# EVK-NORA-W4_SCHEM_0004_Debug_Memory.net
KiCad netlist of a schematic drawn in Altium Designer
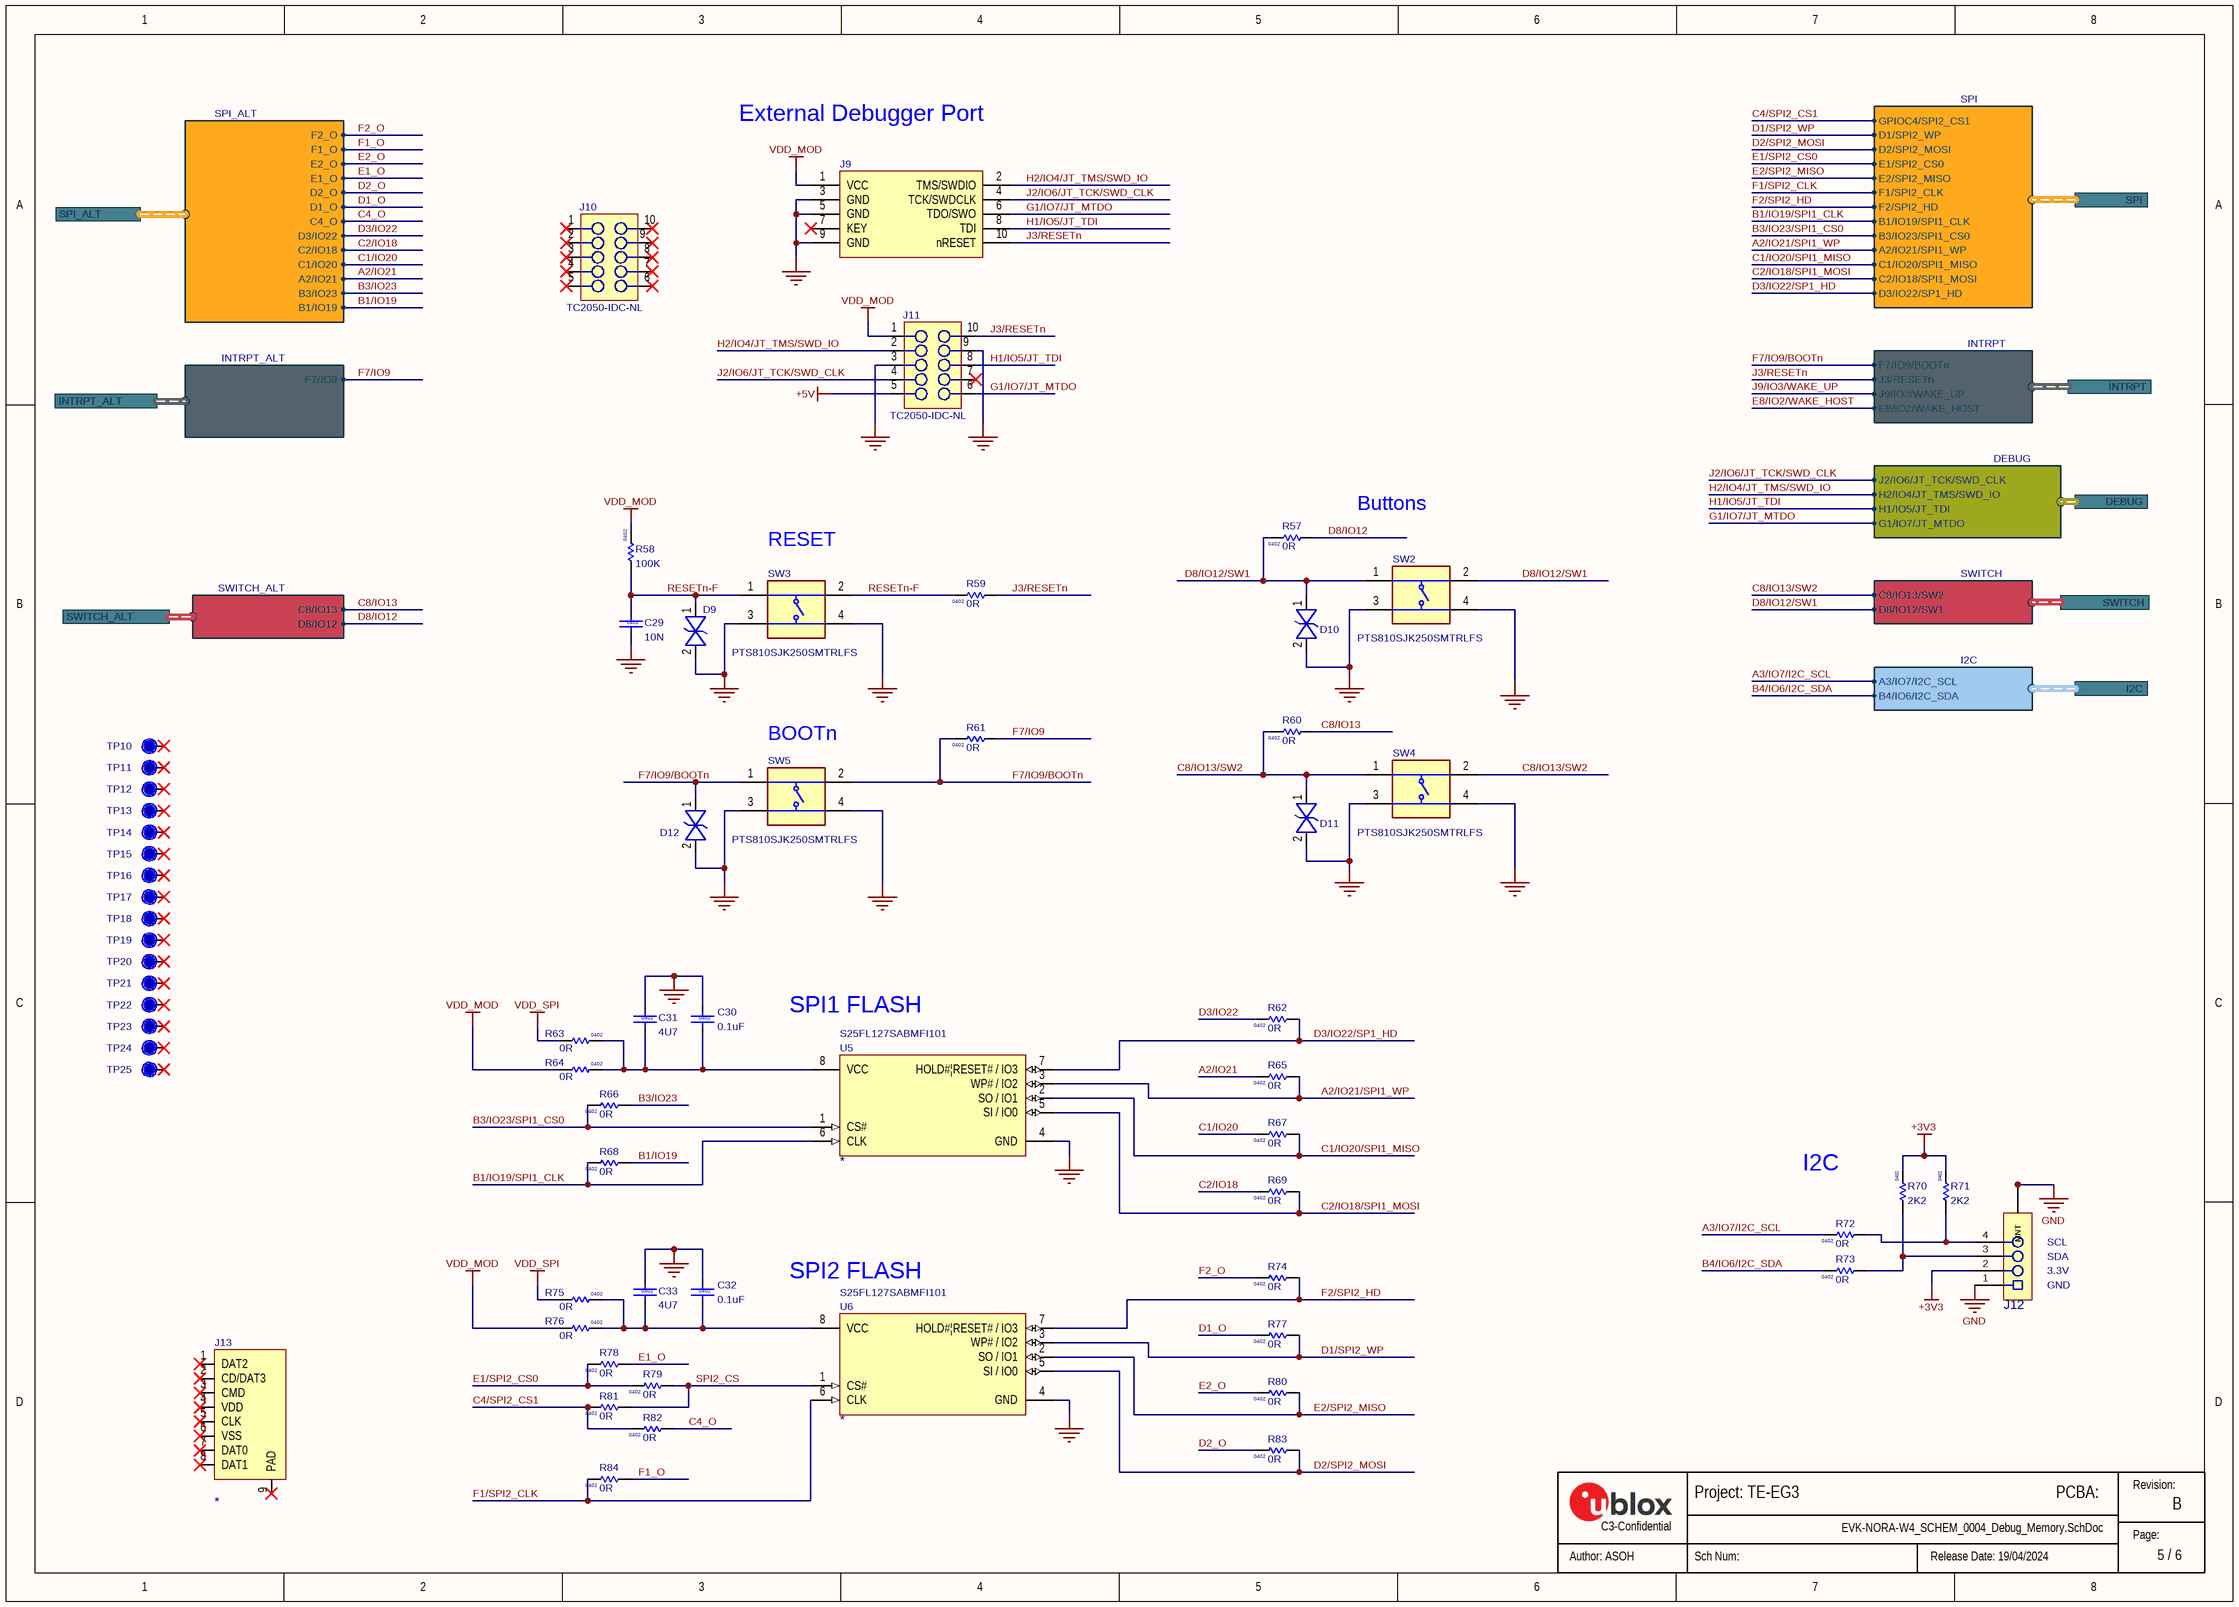
[diagram p0: EVK-NORA-W4_SCHEM_0004_Debug_Memory.SchDoc]

(export (version "E")
  (design (tool "Eeschema 10.0.6"))
  (components
    (comp (ref "C29")
      (value "10N")
      (footprint "Cap_0402_1100Lx600Wx600H_600x600Pad_350G_FLX")
      (description "CAP CER X7R 0402 10N 10% 16V")
      (fields
        (field (name "SIZE") "0402")
        (field (name "PART NUMBER") "UBXH01-0023025")
        (field (name "TOLERANCE") "10%")
        (field (name "EDITOR") "roland.rust")
        (field (name "RELEASED BY") "anthony.gergis")
      )
      (libsource (lib "UBX_Parts_DB_Lib") (part "Cap Chip"))
    )
    (comp (ref "C30")
      (value "0.1uF")
      (footprint "Cap 0402 HD")
      (description "Cap, Ceramic 0.1uF 10V 10% X5R 0402")
      (fields
        (field (name "SIZE") "0402")
        (field (name "PART NUMBER") "120-00016")
        (field (name "MANUFACTURER") "Murata Electronics North America")
      )
      (libsource (lib "Arena_Parts_DB_Lib") (part "Cap Chip"))
    )
    (comp (ref "C31")
      (value "4U7")
      (footprint "Cap 0402 HD")
      (description "CAP CER X5R 0402 4U7 20% 10V")
      (fields
        (field (name "SIZE") "0402")
        (field (name "PART NUMBER") "UBXH01-0000243")
        (field (name "TOLERANCE") "20%")
        (field (name "EDITOR") "martin.pilik")
        (field (name "RELEASED BY") "fabrice.bret-dibat")
      )
      (libsource (lib "UBX_Parts_DB_Lib") (part "Cap Chip"))
    )
    (comp (ref "C32")
      (value "0.1uF")
      (footprint "Cap 0402 HD")
      (description "Cap, Ceramic 0.1uF 10V 10% X5R 0402")
      (fields
        (field (name "SIZE") "0402")
        (field (name "PART NUMBER") "120-00016")
        (field (name "MANUFACTURER") "Murata Electronics North America")
      )
      (libsource (lib "Arena_Parts_DB_Lib") (part "Cap Chip"))
    )
    (comp (ref "C33")
      (value "4U7")
      (footprint "Cap 0402 HD")
      (description "CAP CER X5R 0402 4U7 20% 10V")
      (fields
        (field (name "SIZE") "0402")
        (field (name "PART NUMBER") "UBXH01-0000243")
        (field (name "TOLERANCE") "20%")
        (field (name "EDITOR") "martin.pilik")
        (field (name "RELEASED BY") "fabrice.bret-dibat")
      )
      (libsource (lib "UBX_Parts_DB_Lib") (part "Cap Chip"))
    )
    (comp (ref "D9")
      (value "110-00019")
      (footprint "SOD-923")
      (description "ESD9B3.3ST5G")
      (fields (field (name "MANUFACTURER") "ON Semiconductor") (field (name "VOLTAGE") "3.3V"))
      (libsource (lib "Arena_Parts_DB_Lib") (part "Diode_TVS"))
    )
    (comp (ref "D10")
      (value "110-00019")
      (footprint "SOD-923")
      (description "ESD9B3.3ST5G")
      (fields (field (name "MANUFACTURER") "ON Semiconductor") (field (name "VOLTAGE") "3.3V"))
      (libsource (lib "Arena_Parts_DB_Lib") (part "Diode_TVS"))
    )
    (comp (ref "D11")
      (value "110-00019")
      (footprint "SOD-923")
      (description "ESD9B3.3ST5G")
      (fields (field (name "MANUFACTURER") "ON Semiconductor") (field (name "VOLTAGE") "3.3V"))
      (libsource (lib "Arena_Parts_DB_Lib") (part "Diode_TVS"))
    )
    (comp (ref "D12")
      (value "110-00019")
      (footprint "SOD-923")
      (description "ESD9B3.3ST5G")
      (fields (field (name "MANUFACTURER") "ON Semiconductor") (field (name "VOLTAGE") "3.3V"))
      (libsource (lib "Arena_Parts_DB_Lib") (part "Diode_TVS"))
    )
    (comp (ref "J9")
      (value "130-00099")
      (footprint "HDR.050P-10Pin-2x5-SMT_Key")
      (description "Header 0.05\" 10Pin 2Row SMD Black")
      (fields (field (name "MANUFACTURER") "Samtec"))
      (libsource (lib "Arena_Parts_DB_Lib") (part "JTAG-10Pin"))
    )
    (comp (ref "J10")
      (value "TC2050-IDC-NLDNP")
      (footprint "TC2050-IDC-NL")
      (description "CON PADS FOR CBL PLUG-OF-NAILS 10-PIN NO LEGS")
      (fields
        (field (name "MANUFACTURER P/N") "TC2050-IDC-NL")
        (field (name "PART NUMBER") "TC2050-IDC-NL")
        (field (name "MANUFACTURER") "TAG Connect")
        (field (name "ADDED BY") "Paul B")
      )
      (libsource (lib "LEGACY_Rigado_AltiumLib") (part "CON-10Pin_2Row_ALT"))
    )
    (comp (ref "J11")
      (value "TC2050-IDC-NLDNP")
      (footprint "TC2050-IDC-NL")
      (description "CON PADS FOR CBL PLUG-OF-NAILS 10-PIN NO LEGS")
      (fields
        (field (name "MANUFACTURER P/N") "TC2050-IDC-NL")
        (field (name "PART NUMBER") "TC2050-IDC-NL")
        (field (name "MANUFACTURER") "TAG Connect")
        (field (name "ADDED BY") "Paul B")
      )
      (libsource (lib "LEGACY_Rigado_AltiumLib") (part "CON-10Pin_2Row_ALT"))
    )
    (comp (ref "J12")
      (value "UBXH04-0000797")
      (footprint "SM04B-SRSS-TB")
      (description "CONN JST SH SERIES SMT 4 POS MALE 1MM RA 50V 1A")
      (fields
        (field (name "VOLTAGE") "None")
        (field (name "MANUFACTURER") "JST")
        (field (name "EDITOR") "eric.moog")
      )
      (libsource (lib "UBX_Parts_DB_Lib") (part "SM04B-SRSS-TB"))
    )
    (comp (ref "J13")
      (value "130-00062")
      (footprint "Micro_SD_SKT_SMT_RA")
      (description "Micro SD Card Socket, Right Angle, with 4 Ground Pads, SMT")
      (fields (field (name "MANUFACTURER P/N") "*") (field (name "VOLTAGE") "None"))
      (libsource (lib "Arena_Parts_DB_Lib") (part "SD_Card_SKT"))
    )
    (comp (ref "R57")
      (value "0R")
      (footprint "RES 0402 HD")
      (description "RES THICK FILM CHIP 0402 0R 0 100mW")
      (fields
        (field (name "SIZE") "0402")
        (field (name "PART NUMBER") "UBXH18-0003002")
        (field (name "TOLERANCE") "0")
        (field (name "EDITOR") "charlotte.biber")
        (field (name "RELEASED BY") "peter.mueller")
      )
      (libsource (lib "UBX_Parts_DB_Lib") (part "Res sm"))
    )
    (comp (ref "R58")
      (value "100K")
      (footprint "RES_0402_1100Lx600Wx400H_500x600Pad_400G_FLX")
      (description "RES THICK FILM CHIP 0402 100K 5% 100mW")
      (fields
        (field (name "SIZE") "0402")
        (field (name "PART NUMBER") "UBXH18-0008097")
        (field (name "TOLERANCE") "5%")
        (field (name "EDITOR") "roland.rust")
        (field (name "RELEASED BY") "roland.rust")
      )
      (libsource (lib "UBX_Parts_DB_Lib") (part "Res sm"))
    )
    (comp (ref "R59")
      (value "0R")
      (footprint "RES 0402 HD")
      (description "RES THICK FILM CHIP 0402 0R 0 100mW")
      (fields
        (field (name "SIZE") "0402")
        (field (name "PART NUMBER") "UBXH18-0003002")
        (field (name "TOLERANCE") "0")
        (field (name "EDITOR") "charlotte.biber")
        (field (name "RELEASED BY") "peter.mueller")
      )
      (libsource (lib "UBX_Parts_DB_Lib") (part "Res sm"))
    )
    (comp (ref "R60")
      (value "0R")
      (footprint "RES 0402 HD")
      (description "RES THICK FILM CHIP 0402 0R 0 100mW")
      (fields
        (field (name "SIZE") "0402")
        (field (name "PART NUMBER") "UBXH18-0003002")
        (field (name "TOLERANCE") "0")
        (field (name "EDITOR") "charlotte.biber")
        (field (name "RELEASED BY") "peter.mueller")
      )
      (libsource (lib "UBX_Parts_DB_Lib") (part "Res sm"))
    )
    (comp (ref "R61")
      (value "0R")
      (footprint "RES 0402 HD")
      (description "RES THICK FILM CHIP 0402 0R 0 100mW")
      (fields
        (field (name "SIZE") "0402")
        (field (name "PART NUMBER") "UBXH18-0003002")
        (field (name "TOLERANCE") "0")
        (field (name "EDITOR") "charlotte.biber")
        (field (name "RELEASED BY") "peter.mueller")
      )
      (libsource (lib "UBX_Parts_DB_Lib") (part "Res sm"))
    )
    (comp (ref "R62")
      (value "0R")
      (footprint "RES 0402 HD")
      (description "RES THICK FILM CHIP 0402 0R 0 100mW")
      (fields
        (field (name "SIZE") "0402")
        (field (name "PART NUMBER") "UBXH18-0003002")
        (field (name "TOLERANCE") "0")
        (field (name "EDITOR") "charlotte.biber")
        (field (name "RELEASED BY") "peter.mueller")
      )
      (libsource (lib "UBX_Parts_DB_Lib") (part "Res sm"))
    )
    (comp (ref "R63")
      (value "0R")
      (footprint "RES 0402 HD")
      (description "RES THICK FILM CHIP 0402 0R 0 100mW")
      (fields
        (field (name "SIZE") "0402")
        (field (name "PART NUMBER") "UBXH18-0003002")
        (field (name "TOLERANCE") "0")
        (field (name "EDITOR") "charlotte.biber")
        (field (name "RELEASED BY") "peter.mueller")
      )
      (libsource (lib "UBX_Parts_DB_Lib") (part "Res sm"))
    )
    (comp (ref "R64")
      (value "0R")
      (footprint "RES 0402 HD")
      (description "RES THICK FILM CHIP 0402 0R 0 100mW")
      (fields
        (field (name "SIZE") "0402")
        (field (name "PART NUMBER") "UBXH18-0003002")
        (field (name "TOLERANCE") "0")
        (field (name "EDITOR") "charlotte.biber")
        (field (name "RELEASED BY") "peter.mueller")
      )
      (libsource (lib "UBX_Parts_DB_Lib") (part "Res sm"))
    )
    (comp (ref "R65")
      (value "0R")
      (footprint "RES 0402 HD")
      (description "RES THICK FILM CHIP 0402 0R 0 100mW")
      (fields
        (field (name "SIZE") "0402")
        (field (name "PART NUMBER") "UBXH18-0003002")
        (field (name "TOLERANCE") "0")
        (field (name "EDITOR") "charlotte.biber")
        (field (name "RELEASED BY") "peter.mueller")
      )
      (libsource (lib "UBX_Parts_DB_Lib") (part "Res sm"))
    )
    (comp (ref "R66")
      (value "0R")
      (footprint "RES 0402 HD")
      (description "RES THICK FILM CHIP 0402 0R 0 100mW")
      (fields
        (field (name "SIZE") "0402")
        (field (name "PART NUMBER") "UBXH18-0003002")
        (field (name "TOLERANCE") "0")
        (field (name "EDITOR") "charlotte.biber")
        (field (name "RELEASED BY") "peter.mueller")
      )
      (libsource (lib "UBX_Parts_DB_Lib") (part "Res sm"))
    )
    (comp (ref "R67")
      (value "0R")
      (footprint "RES 0402 HD")
      (description "RES THICK FILM CHIP 0402 0R 0 100mW")
      (fields
        (field (name "SIZE") "0402")
        (field (name "PART NUMBER") "UBXH18-0003002")
        (field (name "TOLERANCE") "0")
        (field (name "EDITOR") "charlotte.biber")
        (field (name "RELEASED BY") "peter.mueller")
      )
      (libsource (lib "UBX_Parts_DB_Lib") (part "Res sm"))
    )
    (comp (ref "R68")
      (value "0R")
      (footprint "RES 0402 HD")
      (description "RES THICK FILM CHIP 0402 0R 0 100mW")
      (fields
        (field (name "SIZE") "0402")
        (field (name "PART NUMBER") "UBXH18-0003002")
        (field (name "TOLERANCE") "0")
        (field (name "EDITOR") "charlotte.biber")
        (field (name "RELEASED BY") "peter.mueller")
      )
      (libsource (lib "UBX_Parts_DB_Lib") (part "Res sm"))
    )
    (comp (ref "R69")
      (value "0R")
      (footprint "RES 0402 HD")
      (description "RES THICK FILM CHIP 0402 0R 0 100mW")
      (fields
        (field (name "SIZE") "0402")
        (field (name "PART NUMBER") "UBXH18-0003002")
        (field (name "TOLERANCE") "0")
        (field (name "EDITOR") "charlotte.biber")
        (field (name "RELEASED BY") "peter.mueller")
      )
      (libsource (lib "UBX_Parts_DB_Lib") (part "Res sm"))
    )
    (comp (ref "R70")
      (value "2K2")
      (footprint "RES_0402_1100Lx600Wx400H_500x600Pad_400G_FLX")
      (description "RES THICK FILM CHIP 0402 2K2 5% 100mW")
      (fields
        (field (name "SIZE") "0402")
        (field (name "PART NUMBER") "UBXH18-0008057")
        (field (name "TOLERANCE") "5%")
        (field (name "EDITOR") "roland.rust")
        (field (name "RELEASED BY") "roland.rust")
      )
      (libsource (lib "UBX_Parts_DB_Lib") (part "Res sm"))
    )
    (comp (ref "R71")
      (value "2K2")
      (footprint "RES_0402_1100Lx600Wx400H_500x600Pad_400G_FLX")
      (description "RES THICK FILM CHIP 0402 2K2 5% 100mW")
      (fields
        (field (name "SIZE") "0402")
        (field (name "PART NUMBER") "UBXH18-0008057")
        (field (name "TOLERANCE") "5%")
        (field (name "EDITOR") "roland.rust")
        (field (name "RELEASED BY") "roland.rust")
      )
      (libsource (lib "UBX_Parts_DB_Lib") (part "Res sm"))
    )
    (comp (ref "R72")
      (value "0R")
      (footprint "RES 0402 HD")
      (description "RES THICK FILM CHIP 0402 0R 0 100mW")
      (fields
        (field (name "SIZE") "0402")
        (field (name "PART NUMBER") "UBXH18-0003002")
        (field (name "TOLERANCE") "0")
        (field (name "EDITOR") "charlotte.biber")
        (field (name "RELEASED BY") "peter.mueller")
      )
      (libsource (lib "UBX_Parts_DB_Lib") (part "Res sm"))
    )
    (comp (ref "R73")
      (value "0R")
      (footprint "RES 0402 HD")
      (description "RES THICK FILM CHIP 0402 0R 0 100mW")
      (fields
        (field (name "SIZE") "0402")
        (field (name "PART NUMBER") "UBXH18-0003002")
        (field (name "TOLERANCE") "0")
        (field (name "EDITOR") "charlotte.biber")
        (field (name "RELEASED BY") "peter.mueller")
      )
      (libsource (lib "UBX_Parts_DB_Lib") (part "Res sm"))
    )
    (comp (ref "R74")
      (value "0R")
      (footprint "RES 0402 HD")
      (description "RES THICK FILM CHIP 0402 0R 0 100mW")
      (fields
        (field (name "SIZE") "0402")
        (field (name "PART NUMBER") "UBXH18-0003002")
        (field (name "TOLERANCE") "0")
        (field (name "EDITOR") "charlotte.biber")
        (field (name "RELEASED BY") "peter.mueller")
      )
      (libsource (lib "UBX_Parts_DB_Lib") (part "Res sm"))
    )
    (comp (ref "R75")
      (value "0R")
      (footprint "RES 0402 HD")
      (description "RES THICK FILM CHIP 0402 0R 0 100mW")
      (fields
        (field (name "SIZE") "0402")
        (field (name "PART NUMBER") "UBXH18-0003002")
        (field (name "TOLERANCE") "0")
        (field (name "EDITOR") "charlotte.biber")
        (field (name "RELEASED BY") "peter.mueller")
      )
      (libsource (lib "UBX_Parts_DB_Lib") (part "Res sm"))
    )
    (comp (ref "R76")
      (value "0R")
      (footprint "RES 0402 HD")
      (description "RES THICK FILM CHIP 0402 0R 0 100mW")
      (fields
        (field (name "SIZE") "0402")
        (field (name "PART NUMBER") "UBXH18-0003002")
        (field (name "TOLERANCE") "0")
        (field (name "EDITOR") "charlotte.biber")
        (field (name "RELEASED BY") "peter.mueller")
      )
      (libsource (lib "UBX_Parts_DB_Lib") (part "Res sm"))
    )
    (comp (ref "R77")
      (value "0R")
      (footprint "RES 0402 HD")
      (description "RES THICK FILM CHIP 0402 0R 0 100mW")
      (fields
        (field (name "SIZE") "0402")
        (field (name "PART NUMBER") "UBXH18-0003002")
        (field (name "TOLERANCE") "0")
        (field (name "EDITOR") "charlotte.biber")
        (field (name "RELEASED BY") "peter.mueller")
      )
      (libsource (lib "UBX_Parts_DB_Lib") (part "Res sm"))
    )
    (comp (ref "R78")
      (value "0R")
      (footprint "RES 0402 HD")
      (description "RES THICK FILM CHIP 0402 0R 0 100mW")
      (fields
        (field (name "SIZE") "0402")
        (field (name "PART NUMBER") "UBXH18-0003002")
        (field (name "TOLERANCE") "0")
        (field (name "EDITOR") "charlotte.biber")
        (field (name "RELEASED BY") "peter.mueller")
      )
      (libsource (lib "UBX_Parts_DB_Lib") (part "Res sm"))
    )
    (comp (ref "R79")
      (value "0R")
      (footprint "RES 0402 HD")
      (description "RES THICK FILM CHIP 0402 0R 0 100mW")
      (fields
        (field (name "SIZE") "0402")
        (field (name "PART NUMBER") "UBXH18-0003002")
        (field (name "TOLERANCE") "0")
        (field (name "EDITOR") "charlotte.biber")
        (field (name "RELEASED BY") "peter.mueller")
      )
      (libsource (lib "UBX_Parts_DB_Lib") (part "Res sm"))
    )
    (comp (ref "R80")
      (value "0R")
      (footprint "RES 0402 HD")
      (description "RES THICK FILM CHIP 0402 0R 0 100mW")
      (fields
        (field (name "SIZE") "0402")
        (field (name "PART NUMBER") "UBXH18-0003002")
        (field (name "TOLERANCE") "0")
        (field (name "EDITOR") "charlotte.biber")
        (field (name "RELEASED BY") "peter.mueller")
      )
      (libsource (lib "UBX_Parts_DB_Lib") (part "Res sm"))
    )
    (comp (ref "R81")
      (value "0R")
      (footprint "RES 0402 HD")
      (description "RES THICK FILM CHIP 0402 0R 0 100mW")
      (fields
        (field (name "SIZE") "0402")
        (field (name "PART NUMBER") "UBXH18-0003002")
        (field (name "TOLERANCE") "0")
        (field (name "EDITOR") "charlotte.biber")
        (field (name "RELEASED BY") "peter.mueller")
      )
      (libsource (lib "UBX_Parts_DB_Lib") (part "Res sm"))
    )
    (comp (ref "R82")
      (value "0R")
      (footprint "RES 0402 HD")
      (description "RES THICK FILM CHIP 0402 0R 0 100mW")
      (fields
        (field (name "SIZE") "0402")
        (field (name "PART NUMBER") "UBXH18-0003002")
        (field (name "TOLERANCE") "0")
        (field (name "EDITOR") "charlotte.biber")
        (field (name "RELEASED BY") "peter.mueller")
      )
      (libsource (lib "UBX_Parts_DB_Lib") (part "Res sm"))
    )
    (comp (ref "R83")
      (value "0R")
      (footprint "RES 0402 HD")
      (description "RES THICK FILM CHIP 0402 0R 0 100mW")
      (fields
        (field (name "SIZE") "0402")
        (field (name "PART NUMBER") "UBXH18-0003002")
        (field (name "TOLERANCE") "0")
        (field (name "EDITOR") "charlotte.biber")
        (field (name "RELEASED BY") "peter.mueller")
      )
      (libsource (lib "UBX_Parts_DB_Lib") (part "Res sm"))
    )
    (comp (ref "R84")
      (value "0R")
      (footprint "RES 0402 HD")
      (description "RES THICK FILM CHIP 0402 0R 0 100mW")
      (fields
        (field (name "SIZE") "0402")
        (field (name "PART NUMBER") "UBXH18-0003002")
        (field (name "TOLERANCE") "0")
        (field (name "EDITOR") "charlotte.biber")
        (field (name "RELEASED BY") "peter.mueller")
      )
      (libsource (lib "UBX_Parts_DB_Lib") (part "Res sm"))
    )
    (comp (ref "SW2")
      (value "PTS810SJK250SMTRLFS")
      (footprint "SamacSys:PTS810SJG250SMTRLFS")
      (description "Switch")
      (fields (field (name "MOUSER PART NUMBER") "611-PTS810SJK250SMTR"))
      (libsource (lib "SamacSys") (part "PTS810SJK250SMTRLFS"))
    )
    (comp (ref "SW3")
      (value "PTS810SJK250SMTRLFS")
      (footprint "SamacSys:PTS810SJG250SMTRLFS")
      (description "Switch")
      (fields (field (name "MOUSER PART NUMBER") "611-PTS810SJK250SMTR"))
      (libsource (lib "SamacSys") (part "PTS810SJK250SMTRLFS"))
    )
    (comp (ref "SW4")
      (value "PTS810SJK250SMTRLFS")
      (footprint "SamacSys:PTS810SJG250SMTRLFS")
      (description "Switch")
      (fields (field (name "MOUSER PART NUMBER") "611-PTS810SJK250SMTR"))
      (libsource (lib "SamacSys") (part "PTS810SJK250SMTRLFS"))
    )
    (comp (ref "SW5")
      (value "PTS810SJK250SMTRLFS")
      (footprint "SamacSys:PTS810SJG250SMTRLFS")
      (description "Switch")
      (fields (field (name "MOUSER PART NUMBER") "611-PTS810SJK250SMTR"))
      (libsource (lib "SamacSys") (part "PTS810SJK250SMTRLFS"))
    )
    (comp (ref "TP10")
      (value "TP")
      (footprint "TP10R")
      (description "Testpoint, Round 1.0mm Dia")
      (fields
        (field (name "PART NUMBER") "TP10R")
        (field (name "ADDED BY") "Jeremy D")
        (field (name "CHECKED BY") "Paul B")
      )
      (libsource (lib "LEGACY_Rigado_AltiumLib") (part "TP_R"))
    )
    (comp (ref "TP11")
      (value "TP")
      (footprint "TP10R")
      (description "Testpoint, Round 1.0mm Dia")
      (fields
        (field (name "PART NUMBER") "TP10R")
        (field (name "ADDED BY") "Jeremy D")
        (field (name "CHECKED BY") "Paul B")
      )
      (libsource (lib "LEGACY_Rigado_AltiumLib") (part "TP_R"))
    )
    (comp (ref "TP12")
      (value "TP")
      (footprint "TP10R")
      (description "Testpoint, Round 1.0mm Dia")
      (fields
        (field (name "PART NUMBER") "TP10R")
        (field (name "ADDED BY") "Jeremy D")
        (field (name "CHECKED BY") "Paul B")
      )
      (libsource (lib "LEGACY_Rigado_AltiumLib") (part "TP_R"))
    )
    (comp (ref "TP13")
      (value "TP")
      (footprint "TP10R")
      (description "Testpoint, Round 1.0mm Dia")
      (fields
        (field (name "PART NUMBER") "TP10R")
        (field (name "ADDED BY") "Jeremy D")
        (field (name "CHECKED BY") "Paul B")
      )
      (libsource (lib "LEGACY_Rigado_AltiumLib") (part "TP_R"))
    )
    (comp (ref "TP14")
      (value "TP")
      (footprint "TP10R")
      (description "Testpoint, Round 1.0mm Dia")
      (fields
        (field (name "PART NUMBER") "TP10R")
        (field (name "ADDED BY") "Jeremy D")
        (field (name "CHECKED BY") "Paul B")
      )
      (libsource (lib "LEGACY_Rigado_AltiumLib") (part "TP_R"))
    )
    (comp (ref "TP15")
      (value "TP")
      (footprint "TP10R")
      (description "Testpoint, Round 1.0mm Dia")
      (fields
        (field (name "PART NUMBER") "TP10R")
        (field (name "ADDED BY") "Jeremy D")
        (field (name "CHECKED BY") "Paul B")
      )
      (libsource (lib "LEGACY_Rigado_AltiumLib") (part "TP_R"))
    )
    (comp (ref "TP16")
      (value "TP")
      (footprint "TP10R")
      (description "Testpoint, Round 1.0mm Dia")
      (fields
        (field (name "PART NUMBER") "TP10R")
        (field (name "ADDED BY") "Jeremy D")
        (field (name "CHECKED BY") "Paul B")
      )
      (libsource (lib "LEGACY_Rigado_AltiumLib") (part "TP_R"))
    )
    (comp (ref "TP17")
      (value "TP")
      (footprint "TP10R")
      (description "Testpoint, Round 1.0mm Dia")
      (fields
        (field (name "PART NUMBER") "TP10R")
        (field (name "ADDED BY") "Jeremy D")
        (field (name "CHECKED BY") "Paul B")
      )
      (libsource (lib "LEGACY_Rigado_AltiumLib") (part "TP_R"))
    )
    (comp (ref "TP18")
      (value "TP")
      (footprint "TP10R")
      (description "Testpoint, Round 1.0mm Dia")
      (fields
        (field (name "PART NUMBER") "TP10R")
        (field (name "ADDED BY") "Jeremy D")
        (field (name "CHECKED BY") "Paul B")
      )
      (libsource (lib "LEGACY_Rigado_AltiumLib") (part "TP_R"))
    )
    (comp (ref "TP19")
      (value "TP")
      (footprint "TP10R")
      (description "Testpoint, Round 1.0mm Dia")
      (fields
        (field (name "PART NUMBER") "TP10R")
        (field (name "ADDED BY") "Jeremy D")
        (field (name "CHECKED BY") "Paul B")
      )
      (libsource (lib "LEGACY_Rigado_AltiumLib") (part "TP_R"))
    )
    (comp (ref "TP20")
      (value "TP")
      (footprint "TP10R")
      (description "Testpoint, Round 1.0mm Dia")
      (fields
        (field (name "PART NUMBER") "TP10R")
        (field (name "ADDED BY") "Jeremy D")
        (field (name "CHECKED BY") "Paul B")
      )
      (libsource (lib "LEGACY_Rigado_AltiumLib") (part "TP_R"))
    )
    (comp (ref "TP21")
      (value "TP")
      (footprint "TP10R")
      (description "Testpoint, Round 1.0mm Dia")
      (fields
        (field (name "PART NUMBER") "TP10R")
        (field (name "ADDED BY") "Jeremy D")
        (field (name "CHECKED BY") "Paul B")
      )
      (libsource (lib "LEGACY_Rigado_AltiumLib") (part "TP_R"))
    )
    (comp (ref "TP22")
      (value "TP")
      (footprint "TP10R")
      (description "Testpoint, Round 1.0mm Dia")
      (fields
        (field (name "PART NUMBER") "TP10R")
        (field (name "ADDED BY") "Jeremy D")
        (field (name "CHECKED BY") "Paul B")
      )
      (libsource (lib "LEGACY_Rigado_AltiumLib") (part "TP_R"))
    )
    (comp (ref "TP23")
      (value "TP")
      (footprint "TP10R")
      (description "Testpoint, Round 1.0mm Dia")
      (fields
        (field (name "PART NUMBER") "TP10R")
        (field (name "ADDED BY") "Jeremy D")
        (field (name "CHECKED BY") "Paul B")
      )
      (libsource (lib "LEGACY_Rigado_AltiumLib") (part "TP_R"))
    )
    (comp (ref "TP24")
      (value "TP")
      (footprint "TP10R")
      (description "Testpoint, Round 1.0mm Dia")
      (fields
        (field (name "PART NUMBER") "TP10R")
        (field (name "ADDED BY") "Jeremy D")
        (field (name "CHECKED BY") "Paul B")
      )
      (libsource (lib "LEGACY_Rigado_AltiumLib") (part "TP_R"))
    )
    (comp (ref "TP25")
      (value "TP")
      (footprint "TP10R")
      (description "Testpoint, Round 1.0mm Dia")
      (fields
        (field (name "PART NUMBER") "TP10R")
        (field (name "ADDED BY") "Jeremy D")
        (field (name "CHECKED BY") "Paul B")
      )
      (libsource (lib "LEGACY_Rigado_AltiumLib") (part "TP_R"))
    )
    (comp (ref "U5")
      (value "240-00017")
      (footprint "SOIC-8W")
      (description "IC, Flash 128MBIT, 108MHz, 8SOIC")
      (fields
        (field (name "MANUFACTURER P/N") "*")
        (field (name "MANUFACTURER PART NUMBER 1") "S25FL127SABMFI101")
        (field (name "VOLTAGE") "3.6V")
      )
      (libsource (lib "Arena_Parts_DB_Lib") (part "SPI_Flash_Memory_8Pin"))
    )
    (comp (ref "U6")
      (value "240-00017")
      (footprint "SOIC-8W")
      (description "IC, Flash 128MBIT, 108MHz, 8SOIC")
      (fields
        (field (name "MANUFACTURER P/N") "*")
        (field (name "MANUFACTURER PART NUMBER 1") "S25FL127SABMFI101")
        (field (name "VOLTAGE") "3.6V")
      )
      (libsource (lib "Arena_Parts_DB_Lib") (part "SPI_Flash_Memory_8Pin"))
    )
  )
  (nets
    (net (code "9") (name "+3V3") (class "Default")
      (node (ref "J12") (pin "2") (pinfunction "2_2") (pintype "passive"))
      (node (ref "R70") (pin "2") (pinfunction "2_2") (pintype "passive"))
      (node (ref "R71") (pin "2") (pinfunction "2_2") (pintype "passive"))
    )
    (net (code "10") (name "+5V") (class "Default") (node (ref "J11") (pin "5") (pintype "passive")))
    (net (code "11") (name "/A2{slash}IO21") (class "Default")
      (node (ref "R65") (pin "2") (pinfunction "2_2") (pintype "passive"))
    )
    (net (code "12") (name "/A2{slash}IO21{slash}SPI1_WP") (class "Default")
      (node (ref "R65") (pin "1") (pinfunction "1_1") (pintype "passive"))
      (node (ref "U5") (pin "3") (pinfunction "WP#_/_IO2_3") (pintype "bidirectional"))
    )
    (net (code "13") (name "/A3{slash}IO7{slash}I2C_SCL") (class "Default")
      (node (ref "R72") (pin "2") (pinfunction "2_2") (pintype "passive"))
    )
    (net (code "14") (name "/B1{slash}IO19") (class "Default")
      (node (ref "R68") (pin "1") (pinfunction "1_1") (pintype "passive"))
    )
    (net (code "15") (name "/B1{slash}IO19{slash}SPI1_CLK") (class "Default")
      (node (ref "R68") (pin "2") (pinfunction "2_2") (pintype "passive"))
      (node (ref "U5") (pin "6") (pinfunction "CLK_6") (pintype "input"))
    )
    (net (code "16") (name "/B3{slash}IO23") (class "Default")
      (node (ref "R66") (pin "1") (pinfunction "1_1") (pintype "passive"))
    )
    (net (code "17") (name "/B3{slash}IO23{slash}SPI1_CS0") (class "Default")
      (node (ref "R66") (pin "2") (pinfunction "2_2") (pintype "passive"))
      (node (ref "U5") (pin "1") (pinfunction "CS#_1") (pintype "input"))
    )
    (net (code "18") (name "/B4{slash}IO6{slash}I2C_SDA") (class "Default")
      (node (ref "R73") (pin "2") (pinfunction "2_2") (pintype "passive"))
    )
    (net (code "19") (name "/C1{slash}IO20") (class "Default")
      (node (ref "R67") (pin "2") (pinfunction "2_2") (pintype "passive"))
    )
    (net (code "20") (name "/C1{slash}IO20{slash}SPI1_MISO") (class "Default")
      (node (ref "R67") (pin "1") (pinfunction "1_1") (pintype "passive"))
      (node (ref "U5") (pin "2") (pinfunction "SO_/_IO1_2") (pintype "bidirectional"))
    )
    (net (code "21") (name "/C2{slash}IO18") (class "Default")
      (node (ref "R69") (pin "2") (pinfunction "2_2") (pintype "passive"))
    )
    (net (code "22") (name "/C2{slash}IO18{slash}SPI1_MOSI") (class "Default")
      (node (ref "R69") (pin "1") (pinfunction "1_1") (pintype "passive"))
      (node (ref "U5") (pin "5") (pinfunction "SI_/_IO0_5") (pintype "bidirectional"))
    )
    (net (code "23") (name "/C4_O") (class "Default")
      (node (ref "R82") (pin "1") (pinfunction "1_1") (pintype "passive"))
    )
    (net (code "24") (name "/C4{slash}SPI2_CS1") (class "Default")
      (node (ref "R81") (pin "2") (pinfunction "2_2") (pintype "passive"))
      (node (ref "R82") (pin "2") (pinfunction "2_2") (pintype "passive"))
    )
    (net (code "25") (name "/C8{slash}IO13") (class "Default")
      (node (ref "R60") (pin "1") (pinfunction "1_1") (pintype "passive"))
    )
    (net (code "26") (name "/C8{slash}IO13{slash}SW2") (class "Default")
      (node (ref "D11") (pin "1") (pintype "passive"))
      (node (ref "R60") (pin "2") (pinfunction "2_2") (pintype "passive"))
      (node (ref "SW4") (pin "1") (pinfunction "1_1") (pintype "passive"))
      (node (ref "SW4") (pin "2") (pinfunction "2_2") (pintype "passive"))
    )
    (net (code "27") (name "/D1_O") (class "Default")
      (node (ref "R77") (pin "2") (pinfunction "2_2") (pintype "passive"))
    )
    (net (code "28") (name "/D1{slash}SPI2_WP") (class "Default")
      (node (ref "R77") (pin "1") (pinfunction "1_1") (pintype "passive"))
      (node (ref "U6") (pin "3") (pinfunction "WP#_/_IO2_3") (pintype "bidirectional"))
    )
    (net (code "29") (name "/D2_O") (class "Default")
      (node (ref "R83") (pin "2") (pinfunction "2_2") (pintype "passive"))
    )
    (net (code "30") (name "/D2{slash}SPI2_MOSI") (class "Default")
      (node (ref "R83") (pin "1") (pinfunction "1_1") (pintype "passive"))
      (node (ref "U6") (pin "5") (pinfunction "SI_/_IO0_5") (pintype "bidirectional"))
    )
    (net (code "31") (name "/D3{slash}IO22") (class "Default")
      (node (ref "R62") (pin "2") (pinfunction "2_2") (pintype "passive"))
    )
    (net (code "32") (name "/D3{slash}IO22{slash}SP1_HD") (class "Default")
      (node (ref "R62") (pin "1") (pinfunction "1_1") (pintype "passive"))
      (node (ref "U5") (pin "7") (pinfunction "HOLD#¦RESET#_/_IO3_7") (pintype "bidirectional"))
    )
    (net (code "33") (name "/D8{slash}IO12") (class "Default")
      (node (ref "R57") (pin "1") (pinfunction "1_1") (pintype "passive"))
    )
    (net (code "34") (name "/D8{slash}IO12{slash}SW1") (class "Default")
      (node (ref "D10") (pin "1") (pintype "passive"))
      (node (ref "R57") (pin "2") (pinfunction "2_2") (pintype "passive"))
      (node (ref "SW2") (pin "1") (pinfunction "1_1") (pintype "passive"))
      (node (ref "SW2") (pin "2") (pinfunction "2_2") (pintype "passive"))
    )
    (net (code "35") (name "/E1_O") (class "Default")
      (node (ref "R78") (pin "1") (pinfunction "1_1") (pintype "passive"))
    )
    (net (code "36") (name "/E1{slash}SPI2_CS0") (class "Default")
      (node (ref "R78") (pin "2") (pinfunction "2_2") (pintype "passive"))
      (node (ref "R79") (pin "2") (pinfunction "2_2") (pintype "passive"))
    )
    (net (code "37") (name "/E2_O") (class "Default")
      (node (ref "R80") (pin "2") (pinfunction "2_2") (pintype "passive"))
    )
    (net (code "38") (name "/E2{slash}SPI2_MISO") (class "Default")
      (node (ref "R80") (pin "1") (pinfunction "1_1") (pintype "passive"))
      (node (ref "U6") (pin "2") (pinfunction "SO_/_IO1_2") (pintype "bidirectional"))
    )
    (net (code "40") (name "/F1_O") (class "Default")
      (node (ref "R84") (pin "1") (pinfunction "1_1") (pintype "passive"))
    )
    (net (code "41") (name "/F1{slash}SPI2_CLK") (class "Default")
      (node (ref "R84") (pin "2") (pinfunction "2_2") (pintype "passive"))
      (node (ref "U6") (pin "6") (pinfunction "CLK_6") (pintype "input"))
    )
    (net (code "42") (name "/F2_O") (class "Default")
      (node (ref "R74") (pin "2") (pinfunction "2_2") (pintype "passive"))
    )
    (net (code "43") (name "/F2{slash}SPI2_HD") (class "Default")
      (node (ref "R74") (pin "1") (pinfunction "1_1") (pintype "passive"))
      (node (ref "U6") (pin "7") (pinfunction "HOLD#¦RESET#_/_IO3_7") (pintype "bidirectional"))
    )
    (net (code "44") (name "/F7{slash}IO9") (class "Default")
      (node (ref "R61") (pin "1") (pinfunction "1_1") (pintype "passive"))
    )
    (net (code "45") (name "/F7{slash}IO9{slash}BOOTn") (class "Default")
      (node (ref "D12") (pin "1") (pintype "passive"))
      (node (ref "R61") (pin "2") (pinfunction "2_2") (pintype "passive"))
      (node (ref "SW5") (pin "1") (pinfunction "1_1") (pintype "passive"))
      (node (ref "SW5") (pin "2") (pinfunction "2_2") (pintype "passive"))
    )
    (net (code "46") (name "/G1{slash}IO7{slash}JT_MTDO") (class "Default")
      (node (ref "J11") (pin "6") (pintype "passive"))
      (node (ref "J9") (pin "6") (pinfunction "TDO/SWO_6") (pintype "passive"))
    )
    (net (code "47") (name "/H1{slash}IO5{slash}JT_TDI") (class "Default")
      (node (ref "J11") (pin "8") (pintype "passive"))
      (node (ref "J9") (pin "8") (pinfunction "TDI_8") (pintype "passive"))
    )
    (net (code "48") (name "/H2{slash}IO4{slash}JT_TMS{slash}SWD_IO") (class "Default")
      (node (ref "J11") (pin "2") (pintype "passive"))
      (node (ref "J9") (pin "2") (pinfunction "TMS/SWDIO_2") (pintype "passive"))
    )
    (net (code "49") (name "/J2{slash}IO6{slash}JT_TCK{slash}SWD_CLK") (class "Default")
      (node (ref "J11") (pin "4") (pintype "passive"))
      (node (ref "J9") (pin "4") (pinfunction "TCK/SWDCLK_4") (pintype "passive"))
    )
    (net (code "50") (name "/J3{slash}RESETn") (class "Default")
      (node (ref "J11") (pin "10") (pintype "passive"))
      (node (ref "J9") (pin "10") (pinfunction "nRESET_10") (pintype "passive"))
      (node (ref "R59") (pin "1") (pinfunction "1_1") (pintype "passive"))
    )
    (net (code "52") (name "/RESETn-F") (class "Default")
      (node (ref "C29") (pin "1") (pinfunction "1_1") (pintype "passive"))
      (node (ref "D9") (pin "1") (pintype "passive"))
      (node (ref "R58") (pin "1") (pinfunction "1_1") (pintype "passive"))
      (node (ref "R59") (pin "2") (pinfunction "2_2") (pintype "passive"))
      (node (ref "SW3") (pin "1") (pinfunction "1_1") (pintype "passive"))
      (node (ref "SW3") (pin "2") (pinfunction "2_2") (pintype "passive"))
    )
    (net (code "53") (name "/SPI2_CS") (class "Default")
      (node (ref "R79") (pin "1") (pinfunction "1_1") (pintype "passive"))
      (node (ref "R81") (pin "1") (pinfunction "1_1") (pintype "passive"))
      (node (ref "U6") (pin "1") (pinfunction "CS#_1") (pintype "input"))
    )
    (net (code "62") (name "GND") (class "Default")
      (node (ref "C29") (pin "2") (pinfunction "2_2") (pintype "passive"))
      (node (ref "C30") (pin "1") (pinfunction "1_1") (pintype "passive"))
      (node (ref "C31") (pin "1") (pinfunction "1_1") (pintype "passive"))
      (node (ref "C32") (pin "1") (pinfunction "1_1") (pintype "passive"))
      (node (ref "C33") (pin "1") (pinfunction "1_1") (pintype "passive"))
      (node (ref "D10") (pin "2") (pintype "passive"))
      (node (ref "D11") (pin "2") (pintype "passive"))
      (node (ref "D12") (pin "2") (pintype "passive"))
      (node (ref "D9") (pin "2") (pintype "passive"))
      (node (ref "J11") (pin "3") (pintype "passive"))
      (node (ref "J12") (pin "1") (pinfunction "1_1") (pintype "passive"))
      (node (ref "J12") (pin "M1") (pinfunction "MNT_M1") (pintype "passive"))
      (node (ref "J12") (pin "M2") (pinfunction "MNT_M2") (pintype "passive"))
      (node (ref "J9") (pin "3") (pinfunction "GND_3") (pintype "passive"))
      (node (ref "J9") (pin "5") (pinfunction "GND_5") (pintype "passive"))
      (node (ref "J9") (pin "9") (pinfunction "GND_9") (pintype "passive"))
      (node (ref "SW2") (pin "3") (pinfunction "3_3") (pintype "passive"))
      (node (ref "SW2") (pin "4") (pinfunction "4_4") (pintype "passive"))
      (node (ref "SW3") (pin "3") (pinfunction "3_3") (pintype "passive"))
      (node (ref "SW3") (pin "4") (pinfunction "4_4") (pintype "passive"))
      (node (ref "SW4") (pin "3") (pinfunction "3_3") (pintype "passive"))
      (node (ref "SW4") (pin "4") (pinfunction "4_4") (pintype "passive"))
      (node (ref "SW5") (pin "3") (pinfunction "3_3") (pintype "passive"))
      (node (ref "SW5") (pin "4") (pinfunction "4_4") (pintype "passive"))
      (node (ref "U5") (pin "4") (pinfunction "GND_4") (pintype "power_in"))
      (node (ref "U6") (pin "4") (pinfunction "GND_4") (pintype "power_in"))
    )
    (net (code "63") (name "Net-(J12-Pad3)") (class "Default")
      (node (ref "J12") (pin "3") (pinfunction "3_3") (pintype "passive"))
      (node (ref "R70") (pin "1") (pinfunction "1_1") (pintype "passive"))
      (node (ref "R73") (pin "1") (pinfunction "1_1") (pintype "passive"))
    )
    (net (code "64") (name "Net-(J12-Pad4)") (class "Default")
      (node (ref "J12") (pin "4") (pinfunction "4_4") (pintype "passive"))
      (node (ref "R71") (pin "1") (pinfunction "1_1") (pintype "passive"))
      (node (ref "R72") (pin "1") (pinfunction "1_1") (pintype "passive"))
    )
    (net (code "65") (name "Net-(U5-VCC)") (class "Default")
      (node (ref "C30") (pin "2") (pinfunction "2_2") (pintype "passive"))
      (node (ref "C31") (pin "2") (pinfunction "2_2") (pintype "passive"))
      (node (ref "R63") (pin "2") (pinfunction "2_2") (pintype "passive"))
      (node (ref "R64") (pin "2") (pinfunction "2_2") (pintype "passive"))
      (node (ref "U5") (pin "8") (pinfunction "VCC_8") (pintype "power_in"))
    )
    (net (code "66") (name "Net-(U6-VCC)") (class "Default")
      (node (ref "C32") (pin "2") (pinfunction "2_2") (pintype "passive"))
      (node (ref "C33") (pin "2") (pinfunction "2_2") (pintype "passive"))
      (node (ref "R75") (pin "2") (pinfunction "2_2") (pintype "passive"))
      (node (ref "R76") (pin "2") (pinfunction "2_2") (pintype "passive"))
      (node (ref "U6") (pin "8") (pinfunction "VCC_8") (pintype "power_in"))
    )
    (net (code "67") (name "VDD_MOD") (class "Default")
      (node (ref "J11") (pin "1") (pintype "passive"))
      (node (ref "J9") (pin "1") (pinfunction "VCC_1") (pintype "passive"))
      (node (ref "R58") (pin "2") (pinfunction "2_2") (pintype "passive"))
      (node (ref "R64") (pin "1") (pinfunction "1_1") (pintype "passive"))
      (node (ref "R76") (pin "1") (pinfunction "1_1") (pintype "passive"))
    )
    (net (code "68") (name "VDD_SPI") (class "Default")
      (node (ref "R63") (pin "1") (pinfunction "1_1") (pintype "passive"))
      (node (ref "R75") (pin "1") (pinfunction "1_1") (pintype "passive"))
    )
    (net (code "69") (name "unconnected-(J9-KEY-Pad7)") (class "Default")
      (node (ref "J9") (pin "7") (pinfunction "KEY_7") (pintype "passive+no_connect"))
    )
    (net (code "70") (name "unconnected-(J10-Pad1)") (class "Default")
      (node (ref "J10") (pin "1") (pintype "passive+no_connect"))
    )
    (net (code "71") (name "unconnected-(J10-Pad2)") (class "Default")
      (node (ref "J10") (pin "2") (pintype "passive+no_connect"))
    )
    (net (code "72") (name "unconnected-(J10-Pad3)") (class "Default")
      (node (ref "J10") (pin "3") (pintype "passive+no_connect"))
    )
    (net (code "73") (name "unconnected-(J10-Pad4)") (class "Default")
      (node (ref "J10") (pin "4") (pintype "passive+no_connect"))
    )
    (net (code "74") (name "unconnected-(J10-Pad5)") (class "Default")
      (node (ref "J10") (pin "5") (pintype "passive+no_connect"))
    )
    (net (code "75") (name "unconnected-(J10-Pad6)") (class "Default")
      (node (ref "J10") (pin "6") (pintype "passive+no_connect"))
    )
    (net (code "76") (name "unconnected-(J10-Pad7)") (class "Default")
      (node (ref "J10") (pin "7") (pintype "passive+no_connect"))
    )
    (net (code "77") (name "unconnected-(J10-Pad8)") (class "Default")
      (node (ref "J10") (pin "8") (pintype "passive+no_connect"))
    )
    (net (code "78") (name "unconnected-(J10-Pad9)") (class "Default")
      (node (ref "J10") (pin "9") (pintype "passive"))
    )
    (net (code "79") (name "unconnected-(J10-Pad10)") (class "Default")
      (node (ref "J10") (pin "10") (pintype "passive+no_connect"))
    )
    (net (code "80") (name "unconnected-(J11-Pad7)") (class "Default")
      (node (ref "J11") (pin "7") (pintype "passive+no_connect"))
    )
    (net (code "81") (name "unconnected-(J11-Pad9)") (class "Default")
      (node (ref "J11") (pin "9") (pintype "passive"))
    )
    (net (code "82") (name "unconnected-(J13-CD{slash}DAT3-Pad2)") (class "Default")
      (node (ref "J13") (pin "2") (pinfunction "CD/DAT3_2") (pintype "passive+no_connect"))
    )
    (net (code "83") (name "unconnected-(J13-CLK-Pad5)") (class "Default")
      (node (ref "J13") (pin "5") (pinfunction "CLK_5") (pintype "passive+no_connect"))
    )
    (net (code "84") (name "unconnected-(J13-CMD-Pad3)") (class "Default")
      (node (ref "J13") (pin "3") (pinfunction "CMD_3") (pintype "passive+no_connect"))
    )
    (net (code "85") (name "unconnected-(J13-DAT0-Pad7)") (class "Default")
      (node (ref "J13") (pin "7") (pinfunction "DAT0_7") (pintype "passive+no_connect"))
    )
    (net (code "86") (name "unconnected-(J13-DAT1-Pad8)") (class "Default")
      (node (ref "J13") (pin "8") (pinfunction "DAT1_8") (pintype "passive+no_connect"))
    )
    (net (code "87") (name "unconnected-(J13-DAT2-Pad1)") (class "Default")
      (node (ref "J13") (pin "1") (pinfunction "DAT2_1") (pintype "passive+no_connect"))
    )
    (net (code "88") (name "unconnected-(J13-PAD-Pad9)") (class "Default")
      (node (ref "J13") (pin "9") (pinfunction "PAD_9") (pintype "power_in+no_connect"))
    )
    (net (code "89") (name "unconnected-(J13-VDD-Pad4)") (class "Default")
      (node (ref "J13") (pin "4") (pinfunction "VDD_4") (pintype "power_in+no_connect"))
    )
    (net (code "90") (name "unconnected-(J13-VSS-Pad6)") (class "Default")
      (node (ref "J13") (pin "6") (pinfunction "VSS_6") (pintype "power_in+no_connect"))
    )
    (net (code "91") (name "unconnected-(TP10-Pad1)") (class "Default")
      (node (ref "TP10") (pin "1") (pintype "passive+no_connect"))
    )
    (net (code "92") (name "unconnected-(TP11-Pad1)") (class "Default")
      (node (ref "TP11") (pin "1") (pintype "passive+no_connect"))
    )
    (net (code "93") (name "unconnected-(TP12-Pad1)") (class "Default")
      (node (ref "TP12") (pin "1") (pintype "passive+no_connect"))
    )
    (net (code "94") (name "unconnected-(TP13-Pad1)") (class "Default")
      (node (ref "TP13") (pin "1") (pintype "passive+no_connect"))
    )
    (net (code "95") (name "unconnected-(TP14-Pad1)") (class "Default")
      (node (ref "TP14") (pin "1") (pintype "passive+no_connect"))
    )
    (net (code "96") (name "unconnected-(TP15-Pad1)") (class "Default")
      (node (ref "TP15") (pin "1") (pintype "passive+no_connect"))
    )
    (net (code "97") (name "unconnected-(TP16-Pad1)") (class "Default")
      (node (ref "TP16") (pin "1") (pintype "passive+no_connect"))
    )
    (net (code "98") (name "unconnected-(TP17-Pad1)") (class "Default")
      (node (ref "TP17") (pin "1") (pintype "passive+no_connect"))
    )
    (net (code "99") (name "unconnected-(TP18-Pad1)") (class "Default")
      (node (ref "TP18") (pin "1") (pintype "passive+no_connect"))
    )
    (net (code "100") (name "unconnected-(TP19-Pad1)") (class "Default")
      (node (ref "TP19") (pin "1") (pintype "passive+no_connect"))
    )
    (net (code "101") (name "unconnected-(TP20-Pad1)") (class "Default")
      (node (ref "TP20") (pin "1") (pintype "passive+no_connect"))
    )
    (net (code "102") (name "unconnected-(TP21-Pad1)") (class "Default")
      (node (ref "TP21") (pin "1") (pintype "passive+no_connect"))
    )
    (net (code "103") (name "unconnected-(TP22-Pad1)") (class "Default")
      (node (ref "TP22") (pin "1") (pintype "passive+no_connect"))
    )
    (net (code "104") (name "unconnected-(TP23-Pad1)") (class "Default")
      (node (ref "TP23") (pin "1") (pintype "passive+no_connect"))
    )
    (net (code "105") (name "unconnected-(TP24-Pad1)") (class "Default")
      (node (ref "TP24") (pin "1") (pintype "passive+no_connect"))
    )
    (net (code "106") (name "unconnected-(TP25-Pad1)") (class "Default")
      (node (ref "TP25") (pin "1") (pintype "passive+no_connect"))
    )
  )
)
